# BNSK-Automation-Device.net
KiCad netlist of a schematic drawn in EAGLE
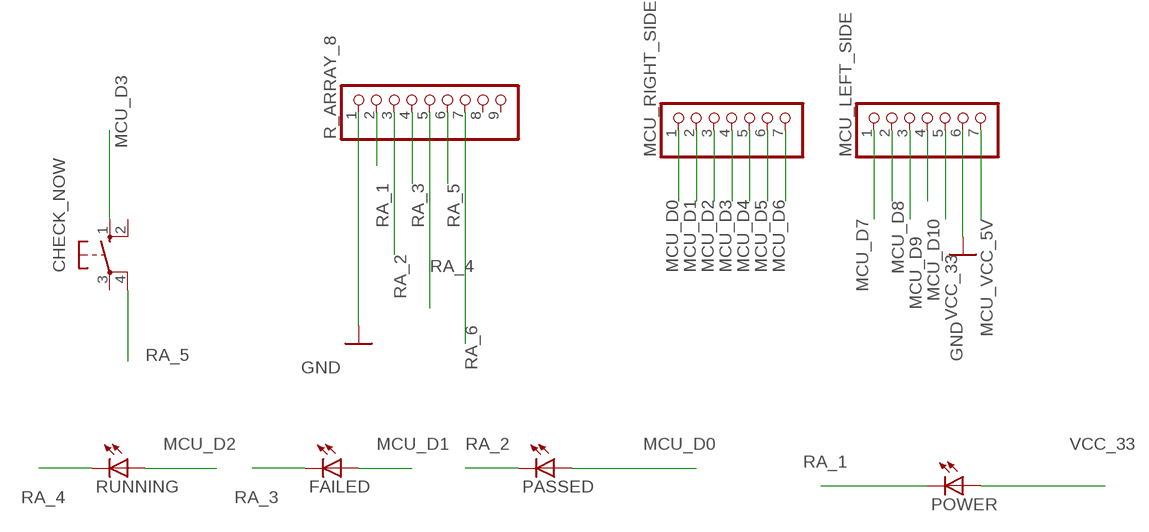
[diagram p0: schematic, sheet 1]

(export (version "E")
  (design (tool "Eeschema 10.0.6"))
  (components
    (comp (ref "CHECK_NOW")
      (value "10-XX")
      (footprint "eagle-import:B3F-10XX")
      (fields (field (name "MPN") "B3F-1000"))
      (libsource (lib "eagle-import") (part "10-XX"))
    )
    (comp (ref "FAILED")
      (value "LEDSMT1206")
      (footprint "eagle-import:1206")
      (libsource (lib "eagle-import") (part "LEDSMT1206"))
    )
    (comp (ref "MCU_LEFT_SIDE")
      (value "PINHD-1X7")
      (footprint "eagle-import:1X07")
      (libsource (lib "eagle-import") (part "PINHD-1X7"))
    )
    (comp (ref "MCU_RIGHT_SIDE")
      (value "PINHD-1X7")
      (footprint "eagle-import:1X07")
      (libsource (lib "eagle-import") (part "PINHD-1X7"))
    )
    (comp (ref "PASSED")
      (value "LEDSMT1206")
      (footprint "eagle-import:1206")
      (libsource (lib "eagle-import") (part "LEDSMT1206"))
    )
    (comp (ref "POWER")
      (value "LEDSMT1206")
      (footprint "eagle-import:1206")
      (libsource (lib "eagle-import") (part "LEDSMT1206"))
    )
    (comp (ref "RUNNING")
      (value "LEDSMT1206")
      (footprint "eagle-import:1206")
      (libsource (lib "eagle-import") (part "LEDSMT1206"))
    )
    (comp (ref "R_ARRAY_8")
      (value "PINHD-1X9")
      (footprint "eagle-import:1X09-BIG")
      (libsource (lib "eagle-import") (part "PINHD-1X9"))
    )
  )
  (nets
    (net (code "1") (name "/MCU_D0") (class "Default")
      (node (ref "MCU_RIGHT_SIDE") (pin "1") (pinfunction "1_1") (pintype "passive"))
      (node (ref "PASSED") (pin "A") (pinfunction "A_A") (pintype "passive"))
    )
    (net (code "2") (name "/MCU_D1") (class "Default")
      (node (ref "FAILED") (pin "A") (pinfunction "A_A") (pintype "passive"))
      (node (ref "MCU_RIGHT_SIDE") (pin "2") (pinfunction "2_2") (pintype "passive"))
    )
    (net (code "3") (name "/MCU_D2") (class "Default")
      (node (ref "MCU_RIGHT_SIDE") (pin "3") (pinfunction "3_3") (pintype "passive"))
      (node (ref "RUNNING") (pin "A") (pinfunction "A_A") (pintype "passive"))
    )
    (net (code "4") (name "/MCU_D3") (class "Default")
      (node (ref "CHECK_NOW") (pin "1") (pinfunction "S_1") (pintype "passive"))
      (node (ref "MCU_RIGHT_SIDE") (pin "4") (pinfunction "4_4") (pintype "passive"))
    )
    (net (code "5") (name "/MCU_D4") (class "Default")
      (node (ref "MCU_RIGHT_SIDE") (pin "5") (pinfunction "5_5") (pintype "passive"))
    )
    (net (code "6") (name "/MCU_D5") (class "Default")
      (node (ref "MCU_RIGHT_SIDE") (pin "6") (pinfunction "6_6") (pintype "passive"))
    )
    (net (code "7") (name "/MCU_D6") (class "Default")
      (node (ref "MCU_RIGHT_SIDE") (pin "7") (pinfunction "7_7") (pintype "passive"))
    )
    (net (code "8") (name "/MCU_D7") (class "Default")
      (node (ref "MCU_LEFT_SIDE") (pin "1") (pinfunction "1_1") (pintype "passive"))
    )
    (net (code "9") (name "/MCU_D8") (class "Default")
      (node (ref "MCU_LEFT_SIDE") (pin "2") (pinfunction "2_2") (pintype "passive"))
    )
    (net (code "10") (name "/MCU_D9") (class "Default")
      (node (ref "MCU_LEFT_SIDE") (pin "3") (pinfunction "3_3") (pintype "passive"))
    )
    (net (code "11") (name "/MCU_D10") (class "Default")
      (node (ref "MCU_LEFT_SIDE") (pin "4") (pinfunction "4_4") (pintype "passive"))
    )
    (net (code "12") (name "/MCU_VCC_5V") (class "Default")
      (node (ref "MCU_LEFT_SIDE") (pin "7") (pinfunction "7_7") (pintype "passive"))
    )
    (net (code "13") (name "/RA_1") (class "Default")
      (node (ref "POWER") (pin "C") (pinfunction "C_C") (pintype "passive"))
      (node (ref "R_ARRAY_8") (pin "2") (pinfunction "2_2") (pintype "passive"))
    )
    (net (code "14") (name "/RA_2") (class "Default")
      (node (ref "PASSED") (pin "C") (pinfunction "C_C") (pintype "passive"))
      (node (ref "R_ARRAY_8") (pin "3") (pinfunction "3_3") (pintype "passive"))
    )
    (net (code "15") (name "/RA_3") (class "Default")
      (node (ref "FAILED") (pin "C") (pinfunction "C_C") (pintype "passive"))
      (node (ref "R_ARRAY_8") (pin "4") (pinfunction "4_4") (pintype "passive"))
    )
    (net (code "16") (name "/RA_4") (class "Default")
      (node (ref "RUNNING") (pin "C") (pinfunction "C_C") (pintype "passive"))
      (node (ref "R_ARRAY_8") (pin "5") (pinfunction "5_5") (pintype "passive"))
    )
    (net (code "17") (name "/RA_5") (class "Default")
      (node (ref "CHECK_NOW") (pin "4") (pinfunction "P1_4") (pintype "passive"))
      (node (ref "R_ARRAY_8") (pin "6") (pinfunction "6_6") (pintype "passive"))
    )
    (net (code "18") (name "/RA_6") (class "Default")
      (node (ref "R_ARRAY_8") (pin "7") (pinfunction "7_7") (pintype "passive"))
    )
    (net (code "19") (name "/VCC_33") (class "Default")
      (node (ref "MCU_LEFT_SIDE") (pin "5") (pinfunction "5_5") (pintype "passive"))
      (node (ref "POWER") (pin "A") (pinfunction "A_A") (pintype "passive"))
    )
    (net (code "20") (name "GND") (class "Default")
      (node (ref "MCU_LEFT_SIDE") (pin "6") (pinfunction "6_6") (pintype "passive"))
      (node (ref "R_ARRAY_8") (pin "1") (pinfunction "1_1") (pintype "passive"))
    )
    (net (code "21") (name "unconnected-(CHECK_NOW-P-Pad3)") (class "Default")
      (node (ref "CHECK_NOW") (pin "3") (pinfunction "P_3") (pintype "passive"))
    )
    (net (code "22") (name "unconnected-(CHECK_NOW-S1-Pad2)") (class "Default")
      (node (ref "CHECK_NOW") (pin "2") (pinfunction "S1_2") (pintype "passive"))
    )
    (net (code "23") (name "unconnected-(R_ARRAY_8-Pad8)") (class "Default")
      (node (ref "R_ARRAY_8") (pin "8") (pinfunction "8_8") (pintype "passive"))
    )
    (net (code "24") (name "unconnected-(R_ARRAY_8-Pad9)") (class "Default")
      (node (ref "R_ARRAY_8") (pin "9") (pinfunction "9_9") (pintype "passive"))
    )
  )
)
